# SchematicSketchFinal.net
KiCad netlist of a schematic drawn in EAGLE
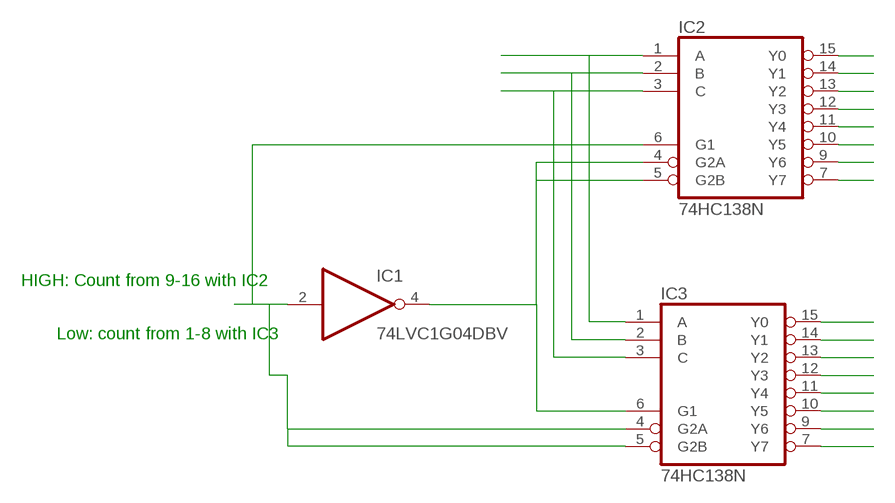
[diagram p0: schematic, sheet 1]

(export (version "E")
  (design (tool "Eeschema 10.0.6"))
  (components
    (comp (ref "IC1")
      (value "74LVC1G04DBV")
      (footprint "eagle-import:SOT23-5")
      (libsource (lib "eagle-import") (part "741G04DBVLVC"))
    )
    (comp (ref "IC2")
      (value "74HC138N")
      (footprint "eagle-import:DIL16")
      (libsource (lib "eagle-import") (part "74138NHC"))
    )
    (comp (ref "IC3")
      (value "74HC138N")
      (footprint "eagle-import:DIL16")
      (libsource (lib "eagle-import") (part "74138NHC"))
    )
  )
  (nets
    (net (code "1") (name "Net-(IC1A-I)") (class "Default")
      (node (ref "IC1") (pin "2") (pinfunction "I_2") (pintype "input"))
      (node (ref "IC2") (pin "6") (pinfunction "G1_6") (pintype "input"))
      (node (ref "IC3") (pin "4") (pinfunction "G2A_4") (pintype "input"))
      (node (ref "IC3") (pin "5") (pinfunction "G2B_5") (pintype "input"))
    )
    (net (code "2") (name "Net-(IC1A-O)") (class "Default")
      (node (ref "IC1") (pin "4") (pinfunction "O_4") (pintype "output"))
      (node (ref "IC2") (pin "4") (pinfunction "G2A_4") (pintype "input"))
      (node (ref "IC2") (pin "5") (pinfunction "G2B_5") (pintype "input"))
      (node (ref "IC3") (pin "6") (pinfunction "G1_6") (pintype "input"))
    )
    (net (code "3") (name "Net-(IC2A-A)") (class "Default")
      (node (ref "IC2") (pin "1") (pinfunction "A_1") (pintype "input"))
      (node (ref "IC3") (pin "1") (pinfunction "A_1") (pintype "input"))
    )
    (net (code "4") (name "Net-(IC2A-B)") (class "Default")
      (node (ref "IC2") (pin "2") (pinfunction "B_2") (pintype "input"))
      (node (ref "IC3") (pin "2") (pinfunction "B_2") (pintype "input"))
    )
    (net (code "5") (name "Net-(IC2A-C)") (class "Default")
      (node (ref "IC2") (pin "3") (pinfunction "C_3") (pintype "input"))
      (node (ref "IC3") (pin "3") (pinfunction "C_3") (pintype "input"))
    )
    (net (code "6") (name "unconnected-(IC2A-Y0-Pad15)") (class "Default")
      (node (ref "IC2") (pin "15") (pinfunction "Y0_15") (pintype "output"))
    )
    (net (code "7") (name "unconnected-(IC2A-Y1-Pad14)") (class "Default")
      (node (ref "IC2") (pin "14") (pinfunction "Y1_14") (pintype "output"))
    )
    (net (code "8") (name "unconnected-(IC2A-Y2-Pad13)") (class "Default")
      (node (ref "IC2") (pin "13") (pinfunction "Y2_13") (pintype "output"))
    )
    (net (code "9") (name "unconnected-(IC2A-Y3-Pad12)") (class "Default")
      (node (ref "IC2") (pin "12") (pinfunction "Y3_12") (pintype "output"))
    )
    (net (code "10") (name "unconnected-(IC2A-Y4-Pad11)") (class "Default")
      (node (ref "IC2") (pin "11") (pinfunction "Y4_11") (pintype "output"))
    )
    (net (code "11") (name "unconnected-(IC2A-Y5-Pad10)") (class "Default")
      (node (ref "IC2") (pin "10") (pinfunction "Y5_10") (pintype "output"))
    )
    (net (code "12") (name "unconnected-(IC2A-Y6-Pad9)") (class "Default")
      (node (ref "IC2") (pin "9") (pinfunction "Y6_9") (pintype "output"))
    )
    (net (code "13") (name "unconnected-(IC2A-Y7-Pad7)") (class "Default")
      (node (ref "IC2") (pin "7") (pinfunction "Y7_7") (pintype "output"))
    )
    (net (code "14") (name "unconnected-(IC3A-Y0-Pad15)") (class "Default")
      (node (ref "IC3") (pin "15") (pinfunction "Y0_15") (pintype "output"))
    )
    (net (code "15") (name "unconnected-(IC3A-Y1-Pad14)") (class "Default")
      (node (ref "IC3") (pin "14") (pinfunction "Y1_14") (pintype "output"))
    )
    (net (code "16") (name "unconnected-(IC3A-Y2-Pad13)") (class "Default")
      (node (ref "IC3") (pin "13") (pinfunction "Y2_13") (pintype "output"))
    )
    (net (code "17") (name "unconnected-(IC3A-Y3-Pad12)") (class "Default")
      (node (ref "IC3") (pin "12") (pinfunction "Y3_12") (pintype "output"))
    )
    (net (code "18") (name "unconnected-(IC3A-Y4-Pad11)") (class "Default")
      (node (ref "IC3") (pin "11") (pinfunction "Y4_11") (pintype "output"))
    )
    (net (code "19") (name "unconnected-(IC3A-Y5-Pad10)") (class "Default")
      (node (ref "IC3") (pin "10") (pinfunction "Y5_10") (pintype "output"))
    )
    (net (code "20") (name "unconnected-(IC3A-Y6-Pad9)") (class "Default")
      (node (ref "IC3") (pin "9") (pinfunction "Y6_9") (pintype "output"))
    )
    (net (code "21") (name "unconnected-(IC3A-Y7-Pad7)") (class "Default")
      (node (ref "IC3") (pin "7") (pinfunction "Y7_7") (pintype "output"))
    )
  )
)
